# 01_Power.net
KiCad netlist of a schematic drawn in Altium Designer
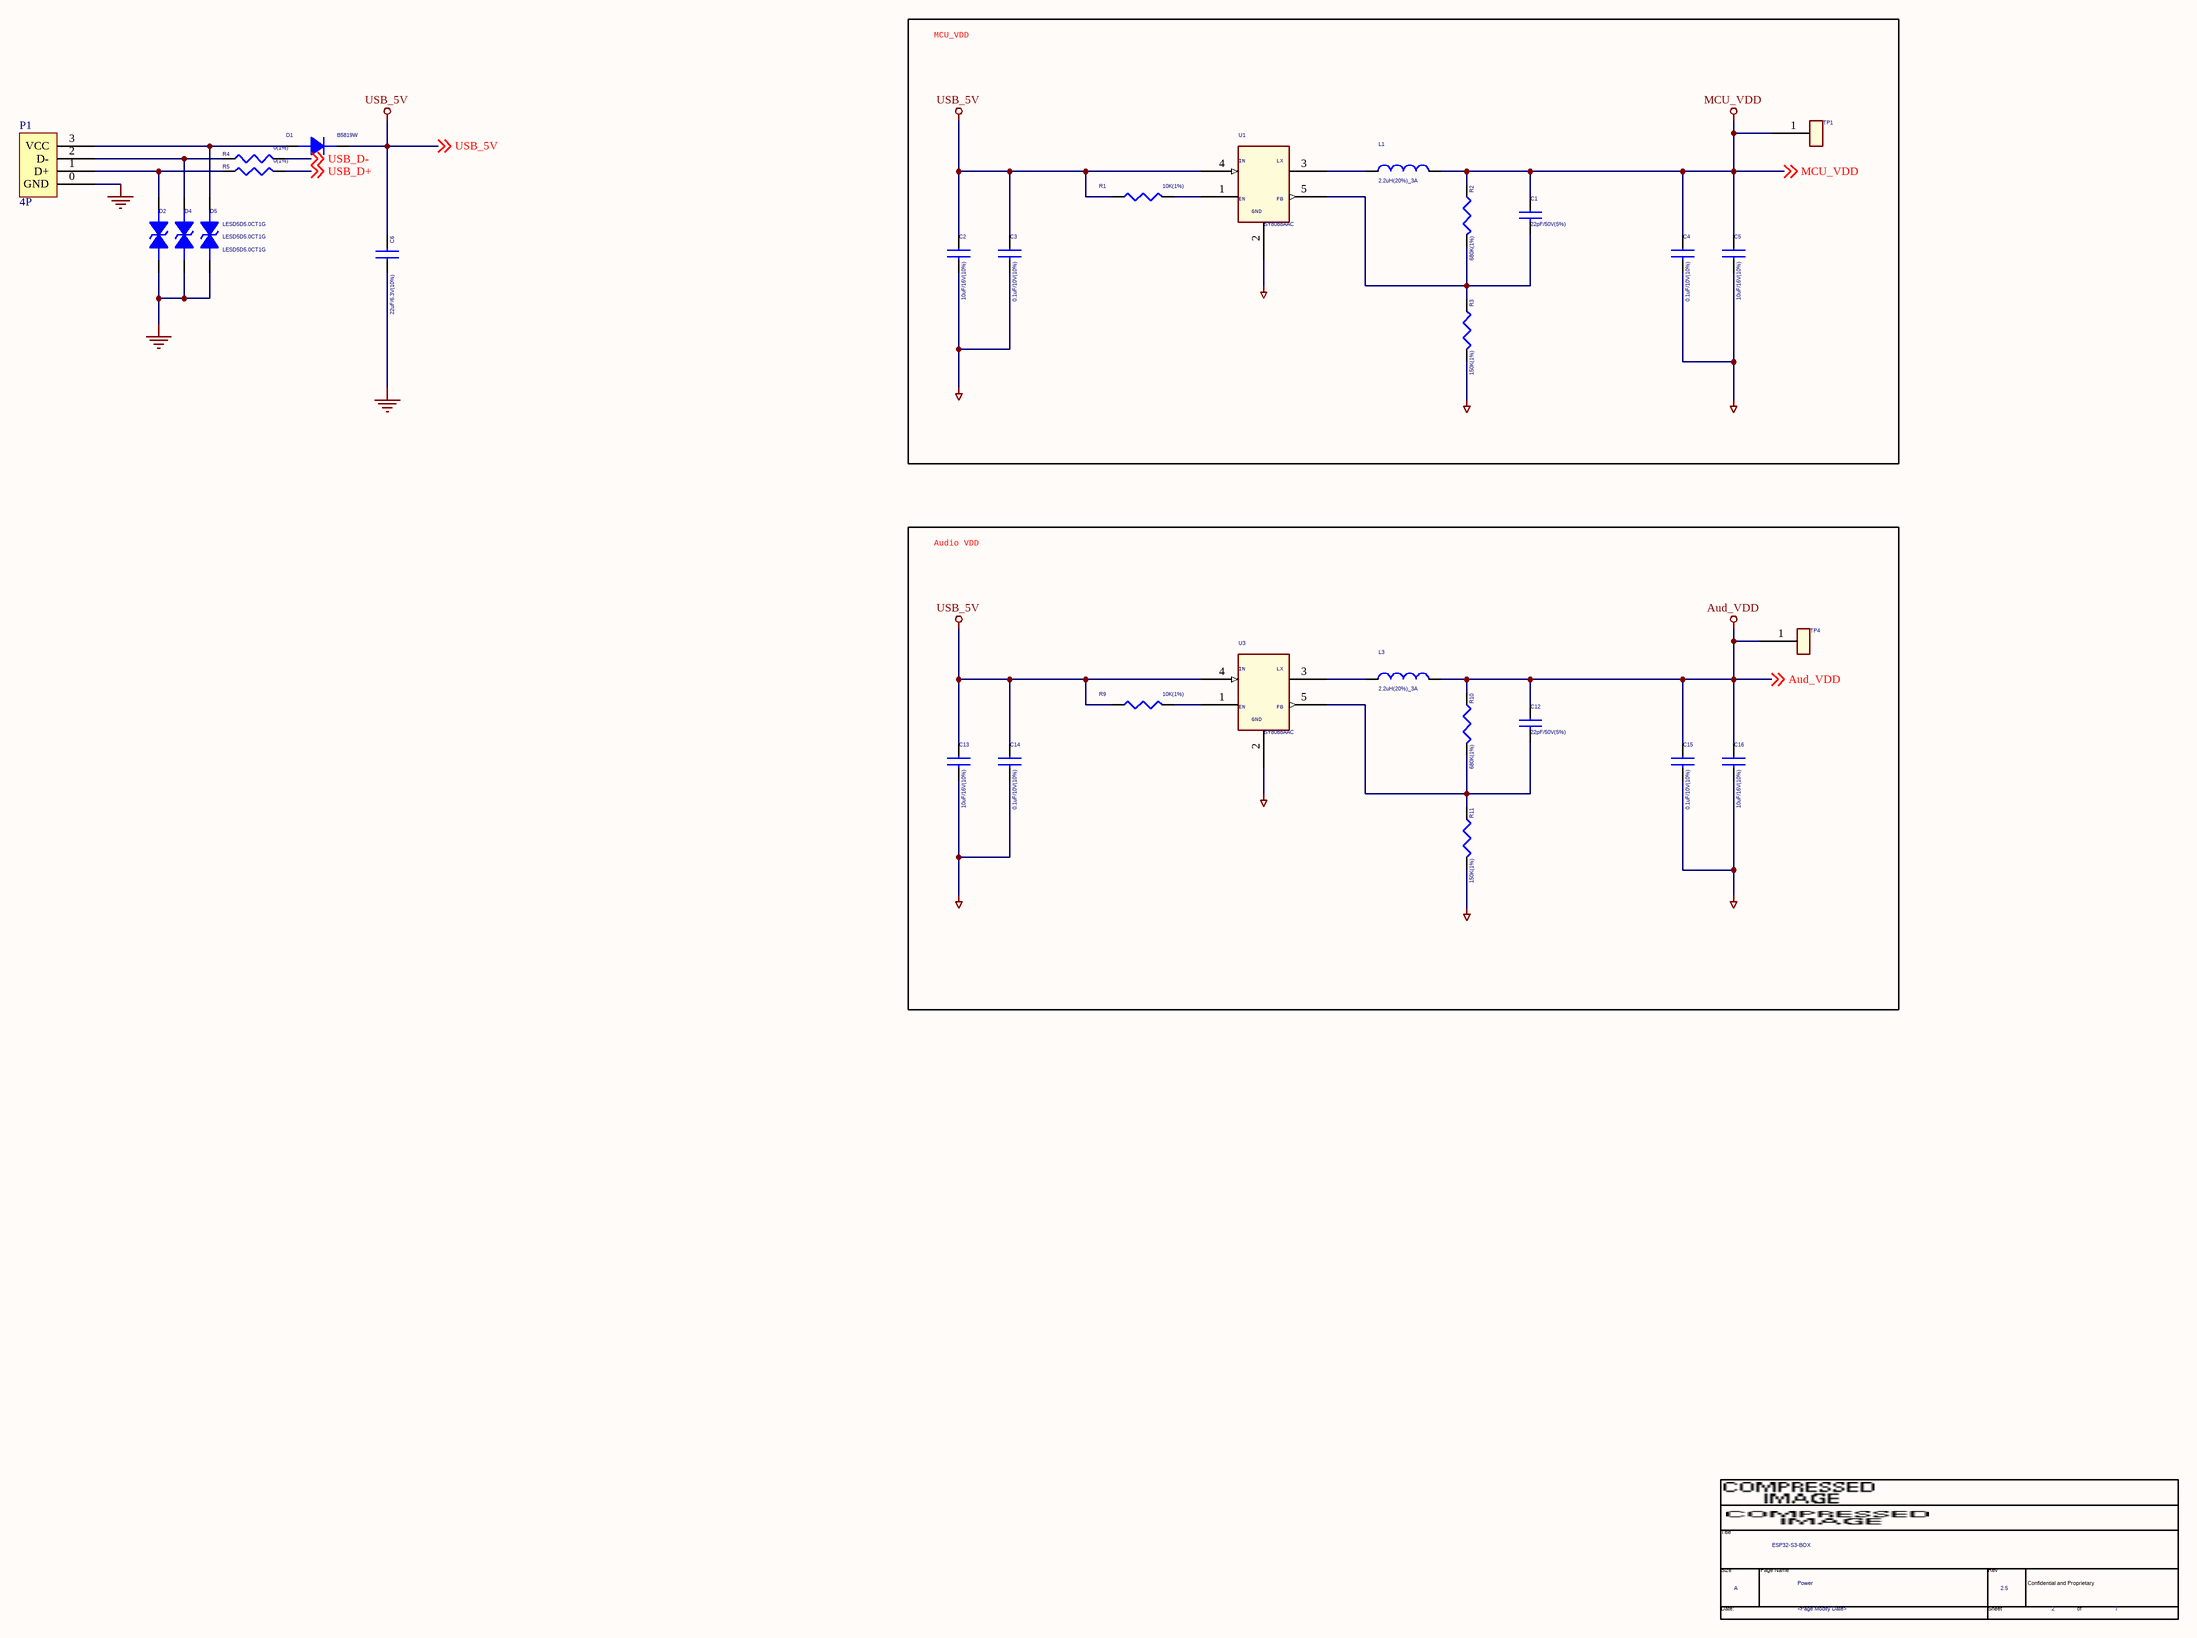
[diagram p0: 01_Power.SchDoc]

(export (version "E")
  (design (tool "Eeschema 10.0.6"))
  (components
    (comp (ref "C1")
      (value "22pF/50V(5%)")
      (footprint "0402_C")
      (fields (field (name "PART NUMBER") "ES11041226520001"))
      (libsource (lib "*") (part "CAPACITOR"))
    )
    (comp (ref "C2")
      (value "10uF/16V(10%)")
      (footprint "0603_C")
      (fields (field (name "PART NUMBER") "ES11067104600000"))
      (libsource (lib "*") (part "CAPACITOR"))
    )
    (comp (ref "C3")
      (value "0.1uF/10V(10%)")
      (footprint "0402_C")
      (fields (field (name "PART NUMBER") "ES11045103620000"))
      (libsource (lib "*") (part "CAPACITOR"))
    )
    (comp (ref "C4")
      (value "0.1uF/10V(10%)")
      (footprint "0402_C")
      (fields (field (name "PART NUMBER") "ES11045103620000"))
      (libsource (lib "*") (part "CAPACITOR"))
    )
    (comp (ref "C5")
      (value "10uF/16V(10%)")
      (footprint "0603_C")
      (fields (field (name "PART NUMBER") "ES11067104600000"))
      (libsource (lib "*") (part "CAPACITOR"))
    )
    (comp (ref "C6")
      (value "22uF/6.3V(10%)")
      (footprint "0603_C")
      (fields (field (name "PART NUMBER") "ES11067222600001"))
      (libsource (lib "*") (part "CAPACITOR"))
    )
    (comp (ref "C12")
      (value "22pF/50V(5%)")
      (footprint "0402_C")
      (fields (field (name "PART NUMBER") "ES11041226520001"))
      (libsource (lib "*") (part "CAPACITOR"))
    )
    (comp (ref "C13")
      (value "10uF/16V(10%)")
      (footprint "0603_C")
      (fields (field (name "PART NUMBER") "ES11067104600000"))
      (libsource (lib "*") (part "CAPACITOR"))
    )
    (comp (ref "C14")
      (value "0.1uF/10V(10%)")
      (footprint "0402_C")
      (fields (field (name "PART NUMBER") "ES11045103620000"))
      (libsource (lib "*") (part "CAPACITOR"))
    )
    (comp (ref "C15")
      (value "0.1uF/10V(10%)")
      (footprint "0402_C")
      (fields (field (name "PART NUMBER") "ES11045103620000"))
      (libsource (lib "*") (part "CAPACITOR"))
    )
    (comp (ref "C16")
      (value "10uF/16V(10%)")
      (footprint "0603_C")
      (fields (field (name "PART NUMBER") "ES11067104600000"))
      (libsource (lib "*") (part "CAPACITOR"))
    )
    (comp (ref "D1")
      (value "B5819W")
      (footprint "SOD-123")
      (fields (field (name "PART NUMBER") "ES31300150000000"))
      (libsource (lib "*") (part "DIODE_S"))
    )
    (comp (ref "D2")
      (value "LESD5D5.0CT1G")
      (footprint "SOD-523")
      (fields (field (name "PART NUMBER") "ES31320020000000"))
      (libsource (lib "*") (part "DIODE_BI_DIR"))
    )
    (comp (ref "D4")
      (value "LESD5D5.0CT1G")
      (footprint "SOD-523")
      (fields (field (name "PART NUMBER") "ES31320020000000"))
      (libsource (lib "*") (part "DIODE_BI_DIR"))
    )
    (comp (ref "D5")
      (value "LESD5D5.0CT1G")
      (footprint "SOD-523")
      (fields (field (name "PART NUMBER") "ES31320020000000"))
      (libsource (lib "*") (part "DIODE_BI_DIR"))
    )
    (comp (ref "L1") (value "2.2uH(20%)_3A") (footprint "L4040") (libsource (lib "*") (part "INDUCTOR_Dup1")))
    (comp (ref "L3") (value "2.2uH(20%)_3A") (footprint "L4040") (libsource (lib "*") (part "INDUCTOR_Dup1")))
    (comp (ref "P1") (value "4P") (footprint "4P") (libsource (lib "supplement") (part "4P")))
    (comp (ref "R1")
      (value "10K(1%)")
      (footprint "0402_R")
      (fields (field (name "PART NUMBER") "ES21044100000001"))
      (libsource (lib "*") (part "RESISTOR"))
    )
    (comp (ref "R2")
      (value "680K(1%)")
      (footprint "0402_R")
      (fields (field (name "PART NUMBER") "ES21045680000001"))
      (libsource (lib "*") (part "RESISTOR"))
    )
    (comp (ref "R3")
      (value "150K(1%)")
      (footprint "0402_R")
      (fields (field (name "PART NUMBER") "ES21045150000001"))
      (libsource (lib "*") (part "RESISTOR"))
    )
    (comp (ref "R4")
      (value "0(1%)")
      (footprint "0201_R")
      (fields (field (name "PART NUMBER") "ES21020000000001"))
      (libsource (lib "*") (part "RESISTOR"))
    )
    (comp (ref "R5")
      (value "0(1%)")
      (footprint "0201_R")
      (fields (field (name "PART NUMBER") "ES21020000000001"))
      (libsource (lib "*") (part "RESISTOR"))
    )
    (comp (ref "R9")
      (value "10K(1%)")
      (footprint "0402_R")
      (fields (field (name "PART NUMBER") "ES21044100000001"))
      (libsource (lib "*") (part "RESISTOR"))
    )
    (comp (ref "R10")
      (value "680K(1%)")
      (footprint "0402_R")
      (fields (field (name "PART NUMBER") "ES21045680000001"))
      (libsource (lib "*") (part "RESISTOR"))
    )
    (comp (ref "R11")
      (value "150K(1%)")
      (footprint "0402_R")
      (fields (field (name "PART NUMBER") "ES21045150000001"))
      (libsource (lib "*") (part "RESISTOR"))
    )
    (comp (ref "TP1") (value "TESTPOINT") (footprint "TPC_D40") (libsource (lib "*") (part "TESTPOINT")))
    (comp (ref "TP4") (value "TESTPOINT") (footprint "TPC_D40") (libsource (lib "*") (part "TESTPOINT")))
    (comp (ref "U1")
      (value "SY8088AAC")
      (footprint "SOT-23-5")
      (fields (field (name "PART NUMBER") "ES41140401000000"))
      (libsource (lib "*") (part "SY808X"))
    )
    (comp (ref "U3")
      (value "SY8088AAC")
      (footprint "SOT-23-5")
      (fields (field (name "PART NUMBER") "ES41140401000000"))
      (libsource (lib "*") (part "SY808X"))
    )
  )
  (nets
    (net (code "1") (name "Aud_VDD") (class "Default")
      (node (ref "C12") (pin "1") (pinfunction "1_1") (pintype "passive"))
      (node (ref "C15") (pin "1") (pinfunction "1_1") (pintype "passive"))
      (node (ref "C16") (pin "1") (pinfunction "1_1") (pintype "passive"))
      (node (ref "L3") (pin "2") (pinfunction "2_2") (pintype "passive"))
      (node (ref "R10") (pin "1") (pinfunction "1_1") (pintype "passive"))
      (node (ref "TP4") (pin "1") (pinfunction "1_1") (pintype "passive"))
    )
    (net (code "2") (name "GND") (class "Default")
      (node (ref "C13") (pin "2") (pinfunction "2_2") (pintype "passive"))
      (node (ref "C14") (pin "2") (pinfunction "2_2") (pintype "passive"))
      (node (ref "C15") (pin "2") (pinfunction "2_2") (pintype "passive"))
      (node (ref "C16") (pin "2") (pinfunction "2_2") (pintype "passive"))
      (node (ref "C2") (pin "2") (pinfunction "2_2") (pintype "passive"))
      (node (ref "C3") (pin "2") (pinfunction "2_2") (pintype "passive"))
      (node (ref "C4") (pin "2") (pinfunction "2_2") (pintype "passive"))
      (node (ref "C5") (pin "2") (pinfunction "2_2") (pintype "passive"))
      (node (ref "C6") (pin "1") (pinfunction "1_1") (pintype "passive"))
      (node (ref "D2") (pin "1") (pinfunction "1_1") (pintype "passive"))
      (node (ref "D4") (pin "1") (pinfunction "1_1") (pintype "passive"))
      (node (ref "D5") (pin "1") (pinfunction "1_1") (pintype "passive"))
      (node (ref "P1") (pin "0") (pinfunction "GND_0") (pintype "passive"))
      (node (ref "R11") (pin "2") (pinfunction "2_2") (pintype "passive"))
      (node (ref "R3") (pin "2") (pinfunction "2_2") (pintype "passive"))
      (node (ref "U1") (pin "2") (pinfunction "GND_2") (pintype "power_in"))
      (node (ref "U3") (pin "2") (pinfunction "GND_2") (pintype "power_in"))
    )
    (net (code "3") (name "MCU_VDD") (class "Default")
      (node (ref "C1") (pin "1") (pinfunction "1_1") (pintype "passive"))
      (node (ref "C4") (pin "1") (pinfunction "1_1") (pintype "passive"))
      (node (ref "C5") (pin "1") (pinfunction "1_1") (pintype "passive"))
      (node (ref "L1") (pin "2") (pinfunction "2_2") (pintype "passive"))
      (node (ref "R2") (pin "1") (pinfunction "1_1") (pintype "passive"))
      (node (ref "TP1") (pin "1") (pinfunction "1_1") (pintype "passive"))
    )
    (net (code "4") (name "Net-(D1-A)") (class "Default")
      (node (ref "D1") (pin "1") (pinfunction "A_1") (pintype "passive"))
      (node (ref "D5") (pin "2") (pinfunction "2_2") (pintype "passive"))
      (node (ref "P1") (pin "3") (pinfunction "VCC_3") (pintype "passive"))
    )
    (net (code "5") (name "Net-(P1-D+)") (class "Default")
      (node (ref "D2") (pin "2") (pinfunction "2_2") (pintype "passive"))
      (node (ref "P1") (pin "1") (pinfunction "D+_1") (pintype "passive"))
      (node (ref "R5") (pin "1") (pinfunction "1_1") (pintype "passive"))
    )
    (net (code "6") (name "Net-(P1-D-)") (class "Default")
      (node (ref "D4") (pin "2") (pinfunction "2_2") (pintype "passive"))
      (node (ref "P1") (pin "2") (pinfunction "D-_2") (pintype "passive"))
      (node (ref "R4") (pin "1") (pinfunction "1_1") (pintype "passive"))
    )
    (net (code "7") (name "Net-(U1-EN)") (class "Default")
      (node (ref "R1") (pin "2") (pinfunction "2_2") (pintype "passive"))
      (node (ref "U1") (pin "1") (pinfunction "EN_1") (pintype "passive"))
    )
    (net (code "8") (name "Net-(U1-FB)") (class "Default")
      (node (ref "C1") (pin "2") (pinfunction "2_2") (pintype "passive"))
      (node (ref "R2") (pin "2") (pinfunction "2_2") (pintype "passive"))
      (node (ref "R3") (pin "1") (pinfunction "1_1") (pintype "passive"))
      (node (ref "U1") (pin "5") (pinfunction "FB_5") (pintype "output"))
    )
    (net (code "9") (name "Net-(U1-LX)") (class "Default")
      (node (ref "L1") (pin "1") (pinfunction "1_1") (pintype "passive"))
      (node (ref "U1") (pin "3") (pinfunction "LX_3") (pintype "passive"))
    )
    (net (code "10") (name "Net-(U3-EN)") (class "Default")
      (node (ref "R9") (pin "2") (pinfunction "2_2") (pintype "passive"))
      (node (ref "U3") (pin "1") (pinfunction "EN_1") (pintype "passive"))
    )
    (net (code "11") (name "Net-(U3-FB)") (class "Default")
      (node (ref "C12") (pin "2") (pinfunction "2_2") (pintype "passive"))
      (node (ref "R10") (pin "2") (pinfunction "2_2") (pintype "passive"))
      (node (ref "R11") (pin "1") (pinfunction "1_1") (pintype "passive"))
      (node (ref "U3") (pin "5") (pinfunction "FB_5") (pintype "output"))
    )
    (net (code "12") (name "Net-(U3-LX)") (class "Default")
      (node (ref "L3") (pin "1") (pinfunction "1_1") (pintype "passive"))
      (node (ref "U3") (pin "3") (pinfunction "LX_3") (pintype "passive"))
    )
    (net (code "13") (name "USB_5V") (class "Default")
      (node (ref "C13") (pin "1") (pinfunction "1_1") (pintype "passive"))
      (node (ref "C14") (pin "1") (pinfunction "1_1") (pintype "passive"))
      (node (ref "C2") (pin "1") (pinfunction "1_1") (pintype "passive"))
      (node (ref "C3") (pin "1") (pinfunction "1_1") (pintype "passive"))
      (node (ref "C6") (pin "2") (pinfunction "2_2") (pintype "passive"))
      (node (ref "D1") (pin "2") (pinfunction "K_2") (pintype "passive"))
      (node (ref "R1") (pin "1") (pinfunction "1_1") (pintype "passive"))
      (node (ref "R9") (pin "1") (pinfunction "1_1") (pintype "passive"))
      (node (ref "U1") (pin "4") (pinfunction "IN_4") (pintype "input"))
      (node (ref "U3") (pin "4") (pinfunction "IN_4") (pintype "input"))
    )
    (net (code "14") (name "USB_D+") (class "Default")
      (node (ref "R5") (pin "2") (pinfunction "2_2") (pintype "passive"))
    )
    (net (code "15") (name "USB_D-") (class "Default")
      (node (ref "R4") (pin "2") (pinfunction "2_2") (pintype "passive"))
    )
  )
)
